# SHARKSKYFC.net
KiCad netlist of a schematic drawn in EAGLE
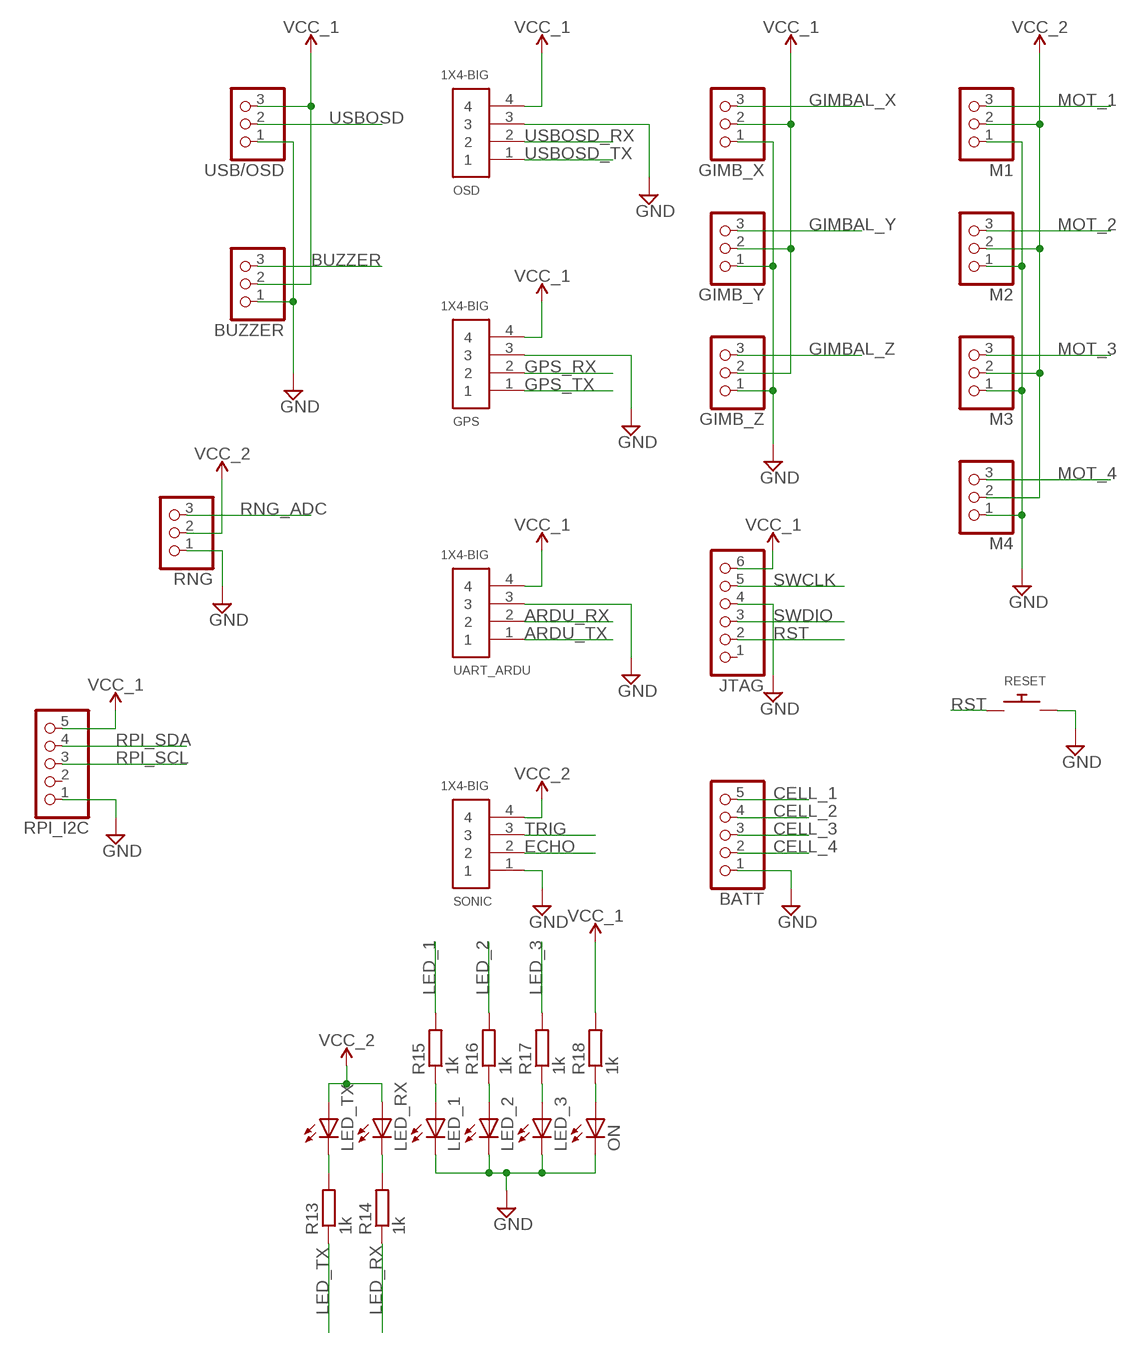
[diagram p0: schematic, sheet 1, part 1 of 2]
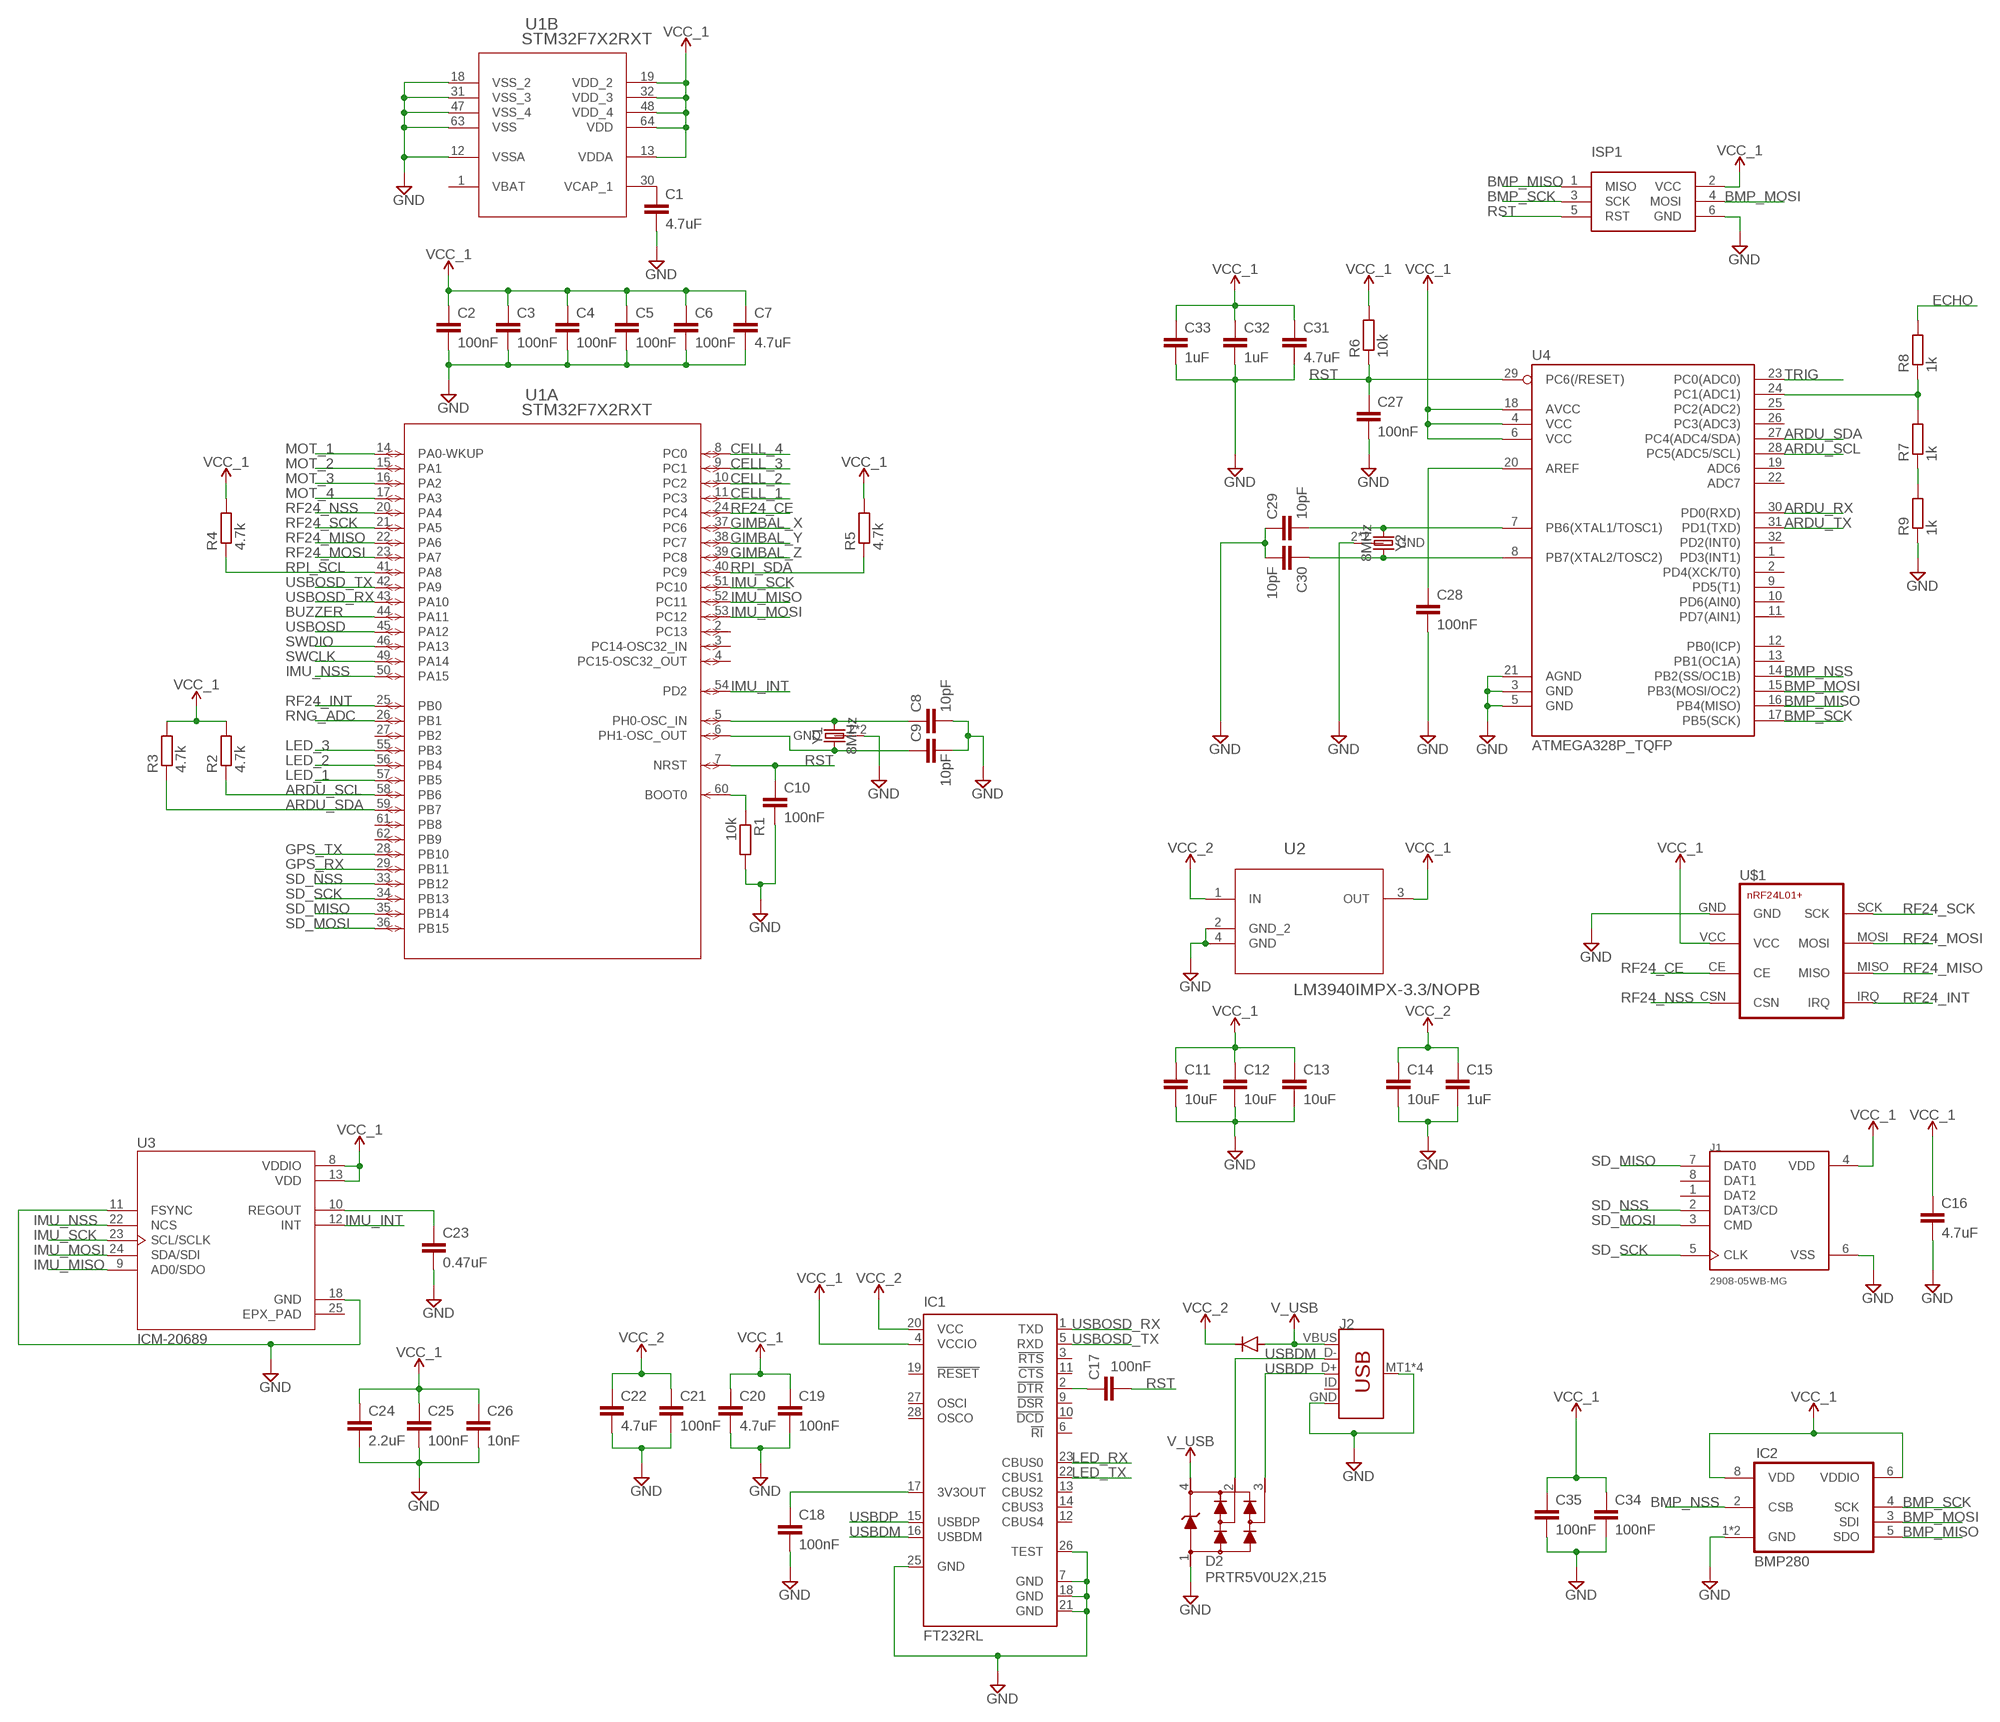
[diagram p1: schematic, sheet 1, part 2 of 2]

(export (version "E")
  (design (tool "Eeschema 10.0.6"))
  (components
    (comp (ref "BATT")
      (value "PINHD-1X5")
      (footprint "eagle-import:1X05")
      (libsource (lib "eagle-import") (part "PINHD-1X5"))
    )
    (comp (ref "BUZZER")
      (value "PINHD-1X3")
      (footprint "eagle-import:1X03")
      (libsource (lib "eagle-import") (part "PINHD-1X3"))
    )
    (comp (ref "C1")
      (value "4.7uF")
      (footprint "eagle-import:C0805")
      (libsource (lib "eagle-import") (part "C-EUC0805"))
    )
    (comp (ref "C2")
      (value "100nF")
      (footprint "eagle-import:C0805")
      (libsource (lib "eagle-import") (part "C-EUC0805"))
    )
    (comp (ref "C3")
      (value "100nF")
      (footprint "eagle-import:C0805")
      (libsource (lib "eagle-import") (part "C-EUC0805"))
    )
    (comp (ref "C4")
      (value "100nF")
      (footprint "eagle-import:C0805")
      (libsource (lib "eagle-import") (part "C-EUC0805"))
    )
    (comp (ref "C5")
      (value "100nF")
      (footprint "eagle-import:C0805")
      (libsource (lib "eagle-import") (part "C-EUC0805"))
    )
    (comp (ref "C6")
      (value "100nF")
      (footprint "eagle-import:C0805")
      (libsource (lib "eagle-import") (part "C-EUC0805"))
    )
    (comp (ref "C7")
      (value "4.7uF")
      (footprint "eagle-import:C0805")
      (libsource (lib "eagle-import") (part "C-EUC0805"))
    )
    (comp (ref "C8")
      (value "10pF")
      (footprint "eagle-import:C0805")
      (libsource (lib "eagle-import") (part "C-EUC0805"))
    )
    (comp (ref "C9")
      (value "10pF")
      (footprint "eagle-import:C0805")
      (libsource (lib "eagle-import") (part "C-EUC0805"))
    )
    (comp (ref "C10")
      (value "100nF")
      (footprint "eagle-import:C0805")
      (libsource (lib "eagle-import") (part "C-EUC0805"))
    )
    (comp (ref "C11")
      (value "10uF")
      (footprint "eagle-import:C0805")
      (libsource (lib "eagle-import") (part "C-EUC0805"))
    )
    (comp (ref "C12")
      (value "10uF")
      (footprint "eagle-import:C0805")
      (libsource (lib "eagle-import") (part "C-EUC0805"))
    )
    (comp (ref "C13")
      (value "10uF")
      (footprint "eagle-import:C0805")
      (libsource (lib "eagle-import") (part "C-EUC0805"))
    )
    (comp (ref "C14")
      (value "10uF")
      (footprint "eagle-import:C0805")
      (libsource (lib "eagle-import") (part "C-EUC0805"))
    )
    (comp (ref "C15")
      (value "1uF")
      (footprint "eagle-import:C0805")
      (libsource (lib "eagle-import") (part "C-EUC0805"))
    )
    (comp (ref "C16")
      (value "4.7uF")
      (footprint "eagle-import:C0805")
      (libsource (lib "eagle-import") (part "C-EUC0805"))
    )
    (comp (ref "C17")
      (value "100nF")
      (footprint "eagle-import:C0805")
      (libsource (lib "eagle-import") (part "C-EUC0805"))
    )
    (comp (ref "C18")
      (value "100nF")
      (footprint "eagle-import:C0805")
      (libsource (lib "eagle-import") (part "C-EUC0805"))
    )
    (comp (ref "C19")
      (value "100nF")
      (footprint "eagle-import:C0805")
      (libsource (lib "eagle-import") (part "C-EUC0805"))
    )
    (comp (ref "C20")
      (value "4.7uF")
      (footprint "eagle-import:C0805")
      (libsource (lib "eagle-import") (part "C-EUC0805"))
    )
    (comp (ref "C21")
      (value "100nF")
      (footprint "eagle-import:C0805")
      (libsource (lib "eagle-import") (part "C-EUC0805"))
    )
    (comp (ref "C22")
      (value "4.7uF")
      (footprint "eagle-import:C0805")
      (libsource (lib "eagle-import") (part "C-EUC0805"))
    )
    (comp (ref "C23")
      (value "0.47uF")
      (footprint "eagle-import:C0805")
      (libsource (lib "eagle-import") (part "C-EUC0805"))
    )
    (comp (ref "C24")
      (value "2.2uF")
      (footprint "eagle-import:C0805")
      (libsource (lib "eagle-import") (part "C-EUC0805"))
    )
    (comp (ref "C25")
      (value "100nF")
      (footprint "eagle-import:C0805")
      (libsource (lib "eagle-import") (part "C-EUC0805"))
    )
    (comp (ref "C26")
      (value "10nF")
      (footprint "eagle-import:C0805")
      (libsource (lib "eagle-import") (part "C-EUC0805"))
    )
    (comp (ref "C27")
      (value "100nF")
      (footprint "eagle-import:C0805")
      (libsource (lib "eagle-import") (part "C-EUC0805"))
    )
    (comp (ref "C28")
      (value "100nF")
      (footprint "eagle-import:C0805")
      (libsource (lib "eagle-import") (part "C-EUC0805"))
    )
    (comp (ref "C29")
      (value "10pF")
      (footprint "eagle-import:C0805")
      (libsource (lib "eagle-import") (part "C-EUC0805"))
    )
    (comp (ref "C30")
      (value "10pF")
      (footprint "eagle-import:C0805")
      (libsource (lib "eagle-import") (part "C-EUC0805"))
    )
    (comp (ref "C31")
      (value "4.7uF")
      (footprint "eagle-import:C0805")
      (libsource (lib "eagle-import") (part "C-EUC0805"))
    )
    (comp (ref "C32")
      (value "1uF")
      (footprint "eagle-import:C0805")
      (libsource (lib "eagle-import") (part "C-EUC0805"))
    )
    (comp (ref "C33")
      (value "1uF")
      (footprint "eagle-import:C0805")
      (libsource (lib "eagle-import") (part "C-EUC0805"))
    )
    (comp (ref "C34")
      (value "100nF")
      (footprint "eagle-import:C0805")
      (libsource (lib "eagle-import") (part "C-EUC0805"))
    )
    (comp (ref "C35")
      (value "100nF")
      (footprint "eagle-import:C0805")
      (libsource (lib "eagle-import") (part "C-EUC0805"))
    )
    (comp (ref "D1")
      (value "DIODE-DO214BA")
      (footprint "eagle-import:DO214BA")
      (libsource (lib "eagle-import") (part "DIODE-DO214BA"))
    )
    (comp (ref "D2")
      (value "PRTR5V0U2X,215")
      (footprint "eagle-import:SOT143B")
      (fields (field (name "MF") "Nexperia USA"))
      (libsource (lib "eagle-import") (part "PRTR5V0U2X,215"))
    )
    (comp (ref "GIMB_X")
      (value "PINHD-1X3")
      (footprint "eagle-import:1X03")
      (libsource (lib "eagle-import") (part "PINHD-1X3"))
    )
    (comp (ref "GIMB_Y")
      (value "PINHD-1X3")
      (footprint "eagle-import:1X03")
      (libsource (lib "eagle-import") (part "PINHD-1X3"))
    )
    (comp (ref "GIMB_Z")
      (value "PINHD-1X3")
      (footprint "eagle-import:1X03")
      (libsource (lib "eagle-import") (part "PINHD-1X3"))
    )
    (comp (ref "GPS")
      (value "1X4-BIG")
      (footprint "eagle-import:1X04-BIG")
      (libsource (lib "eagle-import") (part "1X4-BIG"))
    )
    (comp (ref "IC1")
      (value "FT232RL")
      (footprint "eagle-import:SSOP28")
      (libsource (lib "eagle-import") (part "FT232RL"))
    )
    (comp (ref "IC2")
      (value "BMP280")
      (footprint "eagle-import:BMP280")
      (libsource (lib "eagle-import") (part "BMP280"))
    )
    (comp (ref "ISP1")
      (value "AVRISP-6")
      (footprint "eagle-import:AVRISP")
      (libsource (lib "eagle-import") (part "AVRISP-6"))
    )
    (comp (ref "J1")
      (value "2908-05WB-MG")
      (footprint "eagle-import:3M_2908-05WB-MG")
      (fields (field (name "MF") "3M"))
      (libsource (lib "eagle-import") (part "2908-05WB-MG"))
    )
    (comp (ref "J2")
      (value "USB_MICRO-B_SMT")
      (footprint "eagle-import:USB-MICROB")
      (libsource (lib "eagle-import") (part "USB_MICRO-B_SMT"))
    )
    (comp (ref "JTAG")
      (value "PINHD-1X6")
      (footprint "eagle-import:1X06")
      (libsource (lib "eagle-import") (part "PINHD-1X6"))
    )
    (comp (ref "LED_1")
      (value "LEDSMT1206")
      (footprint "eagle-import:1206")
      (libsource (lib "eagle-import") (part "LEDSMT1206"))
    )
    (comp (ref "LED_2")
      (value "LEDSMT1206")
      (footprint "eagle-import:1206")
      (libsource (lib "eagle-import") (part "LEDSMT1206"))
    )
    (comp (ref "LED_3")
      (value "LEDSMT1206")
      (footprint "eagle-import:1206")
      (libsource (lib "eagle-import") (part "LEDSMT1206"))
    )
    (comp (ref "LED_RX")
      (value "LEDSMT1206")
      (footprint "eagle-import:1206")
      (libsource (lib "eagle-import") (part "LEDSMT1206"))
    )
    (comp (ref "LED_TX")
      (value "LEDSMT1206")
      (footprint "eagle-import:1206")
      (libsource (lib "eagle-import") (part "LEDSMT1206"))
    )
    (comp (ref "M1")
      (value "PINHD-1X3")
      (footprint "eagle-import:1X03")
      (libsource (lib "eagle-import") (part "PINHD-1X3"))
    )
    (comp (ref "M2")
      (value "PINHD-1X3")
      (footprint "eagle-import:1X03")
      (libsource (lib "eagle-import") (part "PINHD-1X3"))
    )
    (comp (ref "M3")
      (value "PINHD-1X3")
      (footprint "eagle-import:1X03")
      (libsource (lib "eagle-import") (part "PINHD-1X3"))
    )
    (comp (ref "M4")
      (value "PINHD-1X3")
      (footprint "eagle-import:1X03")
      (libsource (lib "eagle-import") (part "PINHD-1X3"))
    )
    (comp (ref "ON")
      (value "LEDSMT1206")
      (footprint "eagle-import:1206")
      (libsource (lib "eagle-import") (part "LEDSMT1206"))
    )
    (comp (ref "OSD")
      (value "1X4-BIG")
      (footprint "eagle-import:1X04-BIG")
      (libsource (lib "eagle-import") (part "1X4-BIG"))
    )
    (comp (ref "R1")
      (value "10k")
      (footprint "eagle-import:R0603")
      (libsource (lib "eagle-import") (part "R-EU_R0603"))
    )
    (comp (ref "R2")
      (value "4.7k")
      (footprint "eagle-import:R0603")
      (libsource (lib "eagle-import") (part "R-EU_R0603"))
    )
    (comp (ref "R3")
      (value "4.7k")
      (footprint "eagle-import:R0603")
      (libsource (lib "eagle-import") (part "R-EU_R0603"))
    )
    (comp (ref "R4")
      (value "4.7k")
      (footprint "eagle-import:R0603")
      (libsource (lib "eagle-import") (part "R-EU_R0603"))
    )
    (comp (ref "R5")
      (value "4.7k")
      (footprint "eagle-import:R0603")
      (libsource (lib "eagle-import") (part "R-EU_R0603"))
    )
    (comp (ref "R6")
      (value "10k")
      (footprint "eagle-import:R0603")
      (libsource (lib "eagle-import") (part "R-EU_R0603"))
    )
    (comp (ref "R7")
      (value "1k")
      (footprint "eagle-import:R0603")
      (libsource (lib "eagle-import") (part "R-EU_R0603"))
    )
    (comp (ref "R8")
      (value "1k")
      (footprint "eagle-import:R0603")
      (libsource (lib "eagle-import") (part "R-EU_R0603"))
    )
    (comp (ref "R9")
      (value "1k")
      (footprint "eagle-import:R0603")
      (libsource (lib "eagle-import") (part "R-EU_R0603"))
    )
    (comp (ref "R13")
      (value "1k")
      (footprint "eagle-import:R0603")
      (libsource (lib "eagle-import") (part "R-EU_R0603"))
    )
    (comp (ref "R14")
      (value "1k")
      (footprint "eagle-import:R0603")
      (libsource (lib "eagle-import") (part "R-EU_R0603"))
    )
    (comp (ref "R15")
      (value "1k")
      (footprint "eagle-import:R0603")
      (libsource (lib "eagle-import") (part "R-EU_R0603"))
    )
    (comp (ref "R16")
      (value "1k")
      (footprint "eagle-import:R0603")
      (libsource (lib "eagle-import") (part "R-EU_R0603"))
    )
    (comp (ref "R17")
      (value "1k")
      (footprint "eagle-import:R0603")
      (libsource (lib "eagle-import") (part "R-EU_R0603"))
    )
    (comp (ref "R18")
      (value "1k")
      (footprint "eagle-import:R0603")
      (libsource (lib "eagle-import") (part "R-EU_R0603"))
    )
    (comp (ref "RESET")
      (value "SWITCH_PUSHBUTTONC&K_KSS")
      (footprint "eagle-import:BTN_CK_KSS")
      (libsource (lib "eagle-import") (part "SWITCH_PUSHBUTTONC&K_KSS"))
    )
    (comp (ref "RNG")
      (value "PINHD-1X3")
      (footprint "eagle-import:1X03")
      (libsource (lib "eagle-import") (part "PINHD-1X3"))
    )
    (comp (ref "RPI_I2C")
      (value "PINHD-1X5")
      (footprint "eagle-import:1X05")
      (libsource (lib "eagle-import") (part "PINHD-1X5"))
    )
    (comp (ref "SONIC")
      (value "1X4-BIG")
      (footprint "eagle-import:1X04-BIG")
      (libsource (lib "eagle-import") (part "1X4-BIG"))
    )
    (comp (ref "U$1")
      (value "NRF24L01+")
      (footprint "eagle-import:NRF24L01+")
      (libsource (lib "eagle-import") (part "NRF24L01+"))
    )
    (comp (ref "U1")
      (value "STM32F7X2RXT")
      (footprint "eagle-import:LQFP64-10X10MM")
      (libsource (lib "eagle-import") (part "STM32F7X2RXT"))
    )
    (comp (ref "U2")
      (value "LM3940IMPX-3.3/NOPB")
      (footprint "eagle-import:SOT230P696X180-4N")
      (fields (field (name "MF") "Texas Instruments"))
      (libsource (lib "eagle-import") (part "LM3940IMPX-3.3/NOPB"))
    )
    (comp (ref "U3")
      (value "ICM-20689")
      (footprint "eagle-import:QFN50P400X400X95-25N")
      (fields (field (name "MF") "TDK InvenSense"))
      (libsource (lib "eagle-import") (part "ICM-20689"))
    )
    (comp (ref "U4")
      (value "ATMEGA328P_TQFP")
      (footprint "eagle-import:TQFP32-08")
      (libsource (lib "eagle-import") (part "ATMEGA328P_TQFP"))
    )
    (comp (ref "UART_ARDU")
      (value "1X4-BIG")
      (footprint "eagle-import:1X04-BIG")
      (libsource (lib "eagle-import") (part "1X4-BIG"))
    )
    (comp (ref "USB/OSD")
      (value "PINHD-1X3")
      (footprint "eagle-import:1X03")
      (libsource (lib "eagle-import") (part "PINHD-1X3"))
    )
    (comp (ref "Y1")
      (value "8MHz")
      (footprint "eagle-import:CRYSTAL-SMD-5X3.2-4PAD")
      (libsource (lib "eagle-import") (part "CRYSTAL-8MHZSMD-5X3.2"))
    )
    (comp (ref "Y2")
      (value "8MHz")
      (footprint "eagle-import:CRYSTAL-SMD-5X3.2-4PAD")
      (libsource (lib "eagle-import") (part "CRYSTAL-8MHZSMD-5X3.2"))
    )
  )
  (nets
    (net (code "1") (name "/ARDU_RX") (class "Default")
      (node (ref "U4") (pin "30") (pinfunction "PD0(RXD)_30") (pintype "bidirectional"))
      (node (ref "UART_ARDU") (pin "2") (pinfunction "2_2") (pintype "bidirectional"))
    )
    (net (code "2") (name "/ARDU_SCL") (class "Default")
      (node (ref "R2") (pin "1") (pinfunction "1_1") (pintype "passive"))
      (node (ref "U1") (pin "58") (pinfunction "PB6_58") (pintype "bidirectional"))
      (node (ref "U4") (pin "28") (pinfunction "PC5(ADC5/SCL)_28") (pintype "bidirectional"))
    )
    (net (code "3") (name "/ARDU_SDA") (class "Default")
      (node (ref "R3") (pin "1") (pinfunction "1_1") (pintype "passive"))
      (node (ref "U1") (pin "59") (pinfunction "PB7_59") (pintype "bidirectional"))
      (node (ref "U4") (pin "27") (pinfunction "PC4(ADC4/SDA)_27") (pintype "bidirectional"))
    )
    (net (code "4") (name "/ARDU_TX") (class "Default")
      (node (ref "U4") (pin "31") (pinfunction "PD1(TXD)_31") (pintype "bidirectional"))
      (node (ref "UART_ARDU") (pin "1") (pinfunction "1_1") (pintype "bidirectional"))
    )
    (net (code "5") (name "/BMP_MISO") (class "Default")
      (node (ref "IC2") (pin "5") (pinfunction "SDO_5") (pintype "input"))
      (node (ref "ISP1") (pin "1") (pinfunction "MISO_1") (pintype "input"))
      (node (ref "U4") (pin "16") (pinfunction "PB4(MISO)_16") (pintype "bidirectional"))
    )
    (net (code "6") (name "/BMP_MOSI") (class "Default")
      (node (ref "IC2") (pin "3") (pinfunction "SDI_3") (pintype "bidirectional"))
      (node (ref "ISP1") (pin "4") (pinfunction "MOSI_4") (pintype "output"))
      (node (ref "U4") (pin "15") (pinfunction "PB3(MOSI/OC2)_15") (pintype "bidirectional"))
    )
    (net (code "7") (name "/BMP_NSS") (class "Default")
      (node (ref "IC2") (pin "2") (pinfunction "CSB_2") (pintype "input"))
      (node (ref "U4") (pin "14") (pinfunction "PB2(SS/OC1B)_14") (pintype "bidirectional"))
    )
    (net (code "8") (name "/BMP_SCK") (class "Default")
      (node (ref "IC2") (pin "4") (pinfunction "SCK_4") (pintype "bidirectional"))
      (node (ref "ISP1") (pin "3") (pinfunction "SCK_3") (pintype "output"))
      (node (ref "U4") (pin "17") (pinfunction "PB5(SCK)_17") (pintype "bidirectional"))
    )
    (net (code "9") (name "/BUZZER") (class "Default")
      (node (ref "BUZZER") (pin "3") (pinfunction "3_3") (pintype "passive"))
      (node (ref "U1") (pin "44") (pinfunction "PA11_44") (pintype "bidirectional"))
    )
    (net (code "10") (name "/CELL_1") (class "Default")
      (node (ref "BATT") (pin "5") (pinfunction "5_5") (pintype "passive"))
      (node (ref "U1") (pin "11") (pinfunction "PC3_11") (pintype "bidirectional"))
    )
    (net (code "11") (name "/CELL_2") (class "Default")
      (node (ref "BATT") (pin "4") (pinfunction "4_4") (pintype "passive"))
      (node (ref "U1") (pin "10") (pinfunction "PC2_10") (pintype "bidirectional"))
    )
    (net (code "12") (name "/CELL_3") (class "Default")
      (node (ref "BATT") (pin "3") (pinfunction "3_3") (pintype "passive"))
      (node (ref "U1") (pin "9") (pinfunction "PC1_9") (pintype "bidirectional"))
    )
    (net (code "13") (name "/CELL_4") (class "Default")
      (node (ref "BATT") (pin "2") (pinfunction "2_2") (pintype "passive"))
      (node (ref "U1") (pin "8") (pinfunction "PC0_8") (pintype "bidirectional"))
    )
    (net (code "14") (name "/ECHO") (class "Default")
      (node (ref "R8") (pin "2") (pinfunction "2_2") (pintype "passive"))
      (node (ref "SONIC") (pin "2") (pinfunction "2_2") (pintype "bidirectional"))
    )
    (net (code "15") (name "/EPX_PAD") (class "Default")
      (node (ref "U3") (pin "25") (pinfunction "EPX_PAD_25") (pintype "power_in"))
    )
    (net (code "16") (name "/GIMBAL_X") (class "Default")
      (node (ref "GIMB_X") (pin "3") (pinfunction "3_3") (pintype "passive"))
      (node (ref "U1") (pin "37") (pinfunction "PC6_37") (pintype "bidirectional"))
    )
    (net (code "17") (name "/GIMBAL_Y") (class "Default")
      (node (ref "GIMB_Y") (pin "3") (pinfunction "3_3") (pintype "passive"))
      (node (ref "U1") (pin "38") (pinfunction "PC7_38") (pintype "bidirectional"))
    )
    (net (code "18") (name "/GIMBAL_Z") (class "Default")
      (node (ref "GIMB_Z") (pin "3") (pinfunction "3_3") (pintype "passive"))
      (node (ref "U1") (pin "39") (pinfunction "PC8_39") (pintype "bidirectional"))
    )
    (net (code "19") (name "/GPS_RX") (class "Default")
      (node (ref "GPS") (pin "2") (pinfunction "2_2") (pintype "bidirectional"))
      (node (ref "U1") (pin "29") (pinfunction "PB11_29") (pintype "bidirectional"))
    )
    (net (code "20") (name "/GPS_TX") (class "Default")
      (node (ref "GPS") (pin "1") (pinfunction "1_1") (pintype "bidirectional"))
      (node (ref "U1") (pin "28") (pinfunction "PB10_28") (pintype "bidirectional"))
    )
    (net (code "21") (name "/IMU_INT") (class "Default")
      (node (ref "U1") (pin "54") (pinfunction "PD2_54") (pintype "bidirectional"))
      (node (ref "U3") (pin "12") (pinfunction "INT_12") (pintype "output"))
    )
    (net (code "22") (name "/IMU_MISO") (class "Default")
      (node (ref "U1") (pin "52") (pinfunction "PC11_52") (pintype "bidirectional"))
      (node (ref "U3") (pin "9") (pinfunction "AD0/SDO_9") (pintype "bidirectional"))
    )
    (net (code "23") (name "/IMU_MOSI") (class "Default")
      (node (ref "U1") (pin "53") (pinfunction "PC12_53") (pintype "bidirectional"))
      (node (ref "U3") (pin "24") (pinfunction "SDA/SDI_24") (pintype "bidirectional"))
    )
    (net (code "24") (name "/IMU_NSS") (class "Default")
      (node (ref "U1") (pin "50") (pinfunction "PA15_50") (pintype "bidirectional"))
      (node (ref "U3") (pin "22") (pinfunction "NCS_22") (pintype "input"))
    )
    (net (code "25") (name "/IMU_SCK") (class "Default")
      (node (ref "U1") (pin "51") (pinfunction "PC10_51") (pintype "bidirectional"))
      (node (ref "U3") (pin "23") (pinfunction "SCL/SCLK_23") (pintype "input"))
    )
    (net (code "26") (name "/LED_1") (class "Default")
      (node (ref "R15") (pin "2") (pinfunction "2_2") (pintype "passive"))
      (node (ref "U1") (pin "57") (pinfunction "PB5_57") (pintype "bidirectional"))
    )
    (net (code "27") (name "/LED_2") (class "Default")
      (node (ref "R16") (pin "2") (pinfunction "2_2") (pintype "passive"))
      (node (ref "U1") (pin "56") (pinfunction "PB4_56") (pintype "bidirectional"))
    )
    (net (code "28") (name "/LED_3") (class "Default")
      (node (ref "R17") (pin "2") (pinfunction "2_2") (pintype "passive"))
      (node (ref "U1") (pin "55") (pinfunction "PB3_55") (pintype "bidirectional"))
    )
    (net (code "29") (name "/LED_RX") (class "Default")
      (node (ref "IC1") (pin "23") (pinfunction "CBUS0_23") (pintype "bidirectional"))
      (node (ref "R14") (pin "1") (pinfunction "1_1") (pintype "passive"))
    )
    (net (code "30") (name "/LED_TX") (class "Default")
      (node (ref "IC1") (pin "22") (pinfunction "CBUS1_22") (pintype "bidirectional"))
      (node (ref "R13") (pin "1") (pinfunction "1_1") (pintype "passive"))
    )
    (net (code "31") (name "/MOT_1") (class "Default")
      (node (ref "M1") (pin "3") (pinfunction "3_3") (pintype "passive"))
      (node (ref "U1") (pin "14") (pinfunction "PA0-WKUP_14") (pintype "bidirectional"))
    )
    (net (code "32") (name "/MOT_2") (class "Default")
      (node (ref "M2") (pin "3") (pinfunction "3_3") (pintype "passive"))
      (node (ref "U1") (pin "15") (pinfunction "PA1_15") (pintype "bidirectional"))
    )
    (net (code "33") (name "/MOT_3") (class "Default")
      (node (ref "M3") (pin "3") (pinfunction "3_3") (pintype "passive"))
      (node (ref "U1") (pin "16") (pinfunction "PA2_16") (pintype "bidirectional"))
    )
    (net (code "34") (name "/MOT_4") (class "Default")
      (node (ref "M4") (pin "3") (pinfunction "3_3") (pintype "passive"))
      (node (ref "U1") (pin "17") (pinfunction "PA3_17") (pintype "bidirectional"))
    )
    (net (code "35") (name "/RF24_CE") (class "Default")
      (node (ref "U$1") (pin "CE") (pinfunction "CE_CE") (pintype "bidirectional"))
      (node (ref "U1") (pin "24") (pinfunction "PC4_24") (pintype "bidirectional"))
    )
    (net (code "36") (name "/RF24_INT") (class "Default")
      (node (ref "U$1") (pin "IRQ") (pinfunction "IRQ_IRQ") (pintype "bidirectional"))
      (node (ref "U1") (pin "25") (pinfunction "PB0_25") (pintype "bidirectional"))
    )
    (net (code "37") (name "/RF24_MISO") (class "Default")
      (node (ref "U$1") (pin "MISO") (pinfunction "MISO_MISO") (pintype "bidirectional"))
      (node (ref "U1") (pin "22") (pinfunction "PA6_22") (pintype "bidirectional"))
    )
    (net (code "38") (name "/RF24_MOSI") (class "Default")
      (node (ref "U$1") (pin "MOSI") (pinfunction "MOSI_MOSI") (pintype "bidirectional"))
      (node (ref "U1") (pin "23") (pinfunction "PA7_23") (pintype "bidirectional"))
    )
    (net (code "39") (name "/RF24_NSS") (class "Default")
      (node (ref "U$1") (pin "CSN") (pinfunction "CSN_CSN") (pintype "bidirectional"))
      (node (ref "U1") (pin "20") (pinfunction "PA4_20") (pintype "bidirectional"))
    )
    (net (code "40") (name "/RF24_SCK") (class "Default")
      (node (ref "U$1") (pin "SCK") (pinfunction "SCK_SCK") (pintype "bidirectional"))
      (node (ref "U1") (pin "21") (pinfunction "PA5_21") (pintype "bidirectional"))
    )
    (net (code "41") (name "/RNG_ADC") (class "Default")
      (node (ref "RNG") (pin "3") (pinfunction "3_3") (pintype "passive"))
      (node (ref "U1") (pin "26") (pinfunction "PB1_26") (pintype "bidirectional"))
    )
    (net (code "42") (name "/RPI_SCL") (class "Default")
      (node (ref "R4") (pin "1") (pinfunction "1_1") (pintype "passive"))
      (node (ref "RPI_I2C") (pin "3") (pinfunction "3_3") (pintype "passive"))
      (node (ref "U1") (pin "41") (pinfunction "PA8_41") (pintype "bidirectional"))
    )
    (net (code "43") (name "/RPI_SDA") (class "Default")
      (node (ref "R5") (pin "1") (pinfunction "1_1") (pintype "passive"))
      (node (ref "RPI_I2C") (pin "4") (pinfunction "4_4") (pintype "passive"))
      (node (ref "U1") (pin "40") (pinfunction "PC9_40") (pintype "bidirectional"))
    )
    (net (code "44") (name "/RST") (class "Default")
      (node (ref "C10") (pin "1") (pinfunction "1_1") (pintype "passive"))
      (node (ref "C17") (pin "2") (pinfunction "2_2") (pintype "passive"))
      (node (ref "C27") (pin "1") (pinfunction "1_1") (pintype "passive"))
      (node (ref "ISP1") (pin "5") (pinfunction "RST_5") (pintype "output"))
      (node (ref "JTAG") (pin "2") (pinfunction "2_2") (pintype "passive"))
      (node (ref "R6") (pin "1") (pinfunction "1_1") (pintype "passive"))
      (node (ref "RESET") (pin "P$1") (pinfunction "P$1_P$1") (pintype "passive"))
      (node (ref "U1") (pin "7") (pinfunction "NRST_7") (pintype "bidirectional"))
      (node (ref "U4") (pin "29") (pinfunction "PC6(/RESET)_29") (pintype "bidirectional"))
    )
    (net (code "45") (name "/SD_MISO") (class "Default")
      (node (ref "J1") (pin "7") (pinfunction "DAT0_7") (pintype "bidirectional"))
      (node (ref "U1") (pin "35") (pinfunction "PB14_35") (pintype "bidirectional"))
    )
    (net (code "46") (name "/SD_MOSI") (class "Default")
      (node (ref "J1") (pin "3") (pinfunction "CMD_3") (pintype "bidirectional"))
      (node (ref "U1") (pin "36") (pinfunction "PB15_36") (pintype "bidirectional"))
    )
    (net (code "47") (name "/SD_NSS") (class "Default")
      (node (ref "J1") (pin "2") (pinfunction "DAT3/CD_2") (pintype "bidirectional"))
      (node (ref "U1") (pin "33") (pinfunction "PB12_33") (pintype "bidirectional"))
    )
    (net (code "48") (name "/SD_SCK") (class "Default")
      (node (ref "J1") (pin "5") (pinfunction "CLK_5") (pintype "bidirectional"))
      (node (ref "U1") (pin "34") (pinfunction "PB13_34") (pintype "bidirectional"))
    )
    (net (code "49") (name "/SWCLK") (class "Default")
      (node (ref "JTAG") (pin "5") (pinfunction "5_5") (pintype "passive"))
      (node (ref "U1") (pin "49") (pinfunction "PA14_49") (pintype "bidirectional"))
    )
    (net (code "50") (name "/SWDIO") (class "Default")
      (node (ref "JTAG") (pin "3") (pinfunction "3_3") (pintype "passive"))
      (node (ref "U1") (pin "46") (pinfunction "PA13_46") (pintype "bidirectional"))
    )
    (net (code "51") (name "/TRIG") (class "Default")
      (node (ref "SONIC") (pin "3") (pinfunction "3_3") (pintype "bidirectional"))
      (node (ref "U4") (pin "23") (pinfunction "PC0(ADC0)_23") (pintype "bidirectional"))
    )
    (net (code "52") (name "/USBDM") (class "Default")
      (node (ref "D2") (pin "2") (pinfunction "P$2_2") (pintype "passive"))
      (node (ref "IC1") (pin "16") (pinfunction "USBDM_16") (pintype "bidirectional"))
      (node (ref "J2") (pin "D-") (pinfunction "D-_D-") (pintype "bidirectional"))
    )
    (net (code "53") (name "/USBDP") (class "Default")
      (node (ref "D2") (pin "3") (pinfunction "P$3_3") (pintype "passive"))
      (node (ref "IC1") (pin "15") (pinfunction "USBDP_15") (pintype "bidirectional"))
      (node (ref "J2") (pin "D+") (pinfunction "D+_D+") (pintype "bidirectional"))
    )
    (net (code "54") (name "/USBOSD") (class "Default")
      (node (ref "U1") (pin "45") (pinfunction "PA12_45") (pintype "bidirectional"))
      (node (ref "USB/OSD") (pin "2") (pinfunction "2_2") (pintype "passive"))
    )
    (net (code "55") (name "/USBOSD_RX") (class "Default")
      (node (ref "IC1") (pin "1") (pinfunction "TXD_1") (pintype "output"))
      (node (ref "OSD") (pin "2") (pinfunction "2_2") (pintype "bidirectional"))
      (node (ref "U1") (pin "43") (pinfunction "PA10_43") (pintype "bidirectional"))
    )
    (net (code "56") (name "/USBOSD_TX") (class "Default")
      (node (ref "IC1") (pin "5") (pinfunction "RXD_5") (pintype "input"))
      (node (ref "OSD") (pin "1") (pinfunction "1_1") (pintype "bidirectional"))
      (node (ref "U1") (pin "42") (pinfunction "PA9_42") (pintype "bidirectional"))
    )
    (net (code "57") (name "/VBAT") (class "Default")
      (node (ref "U1") (pin "1") (pinfunction "VBAT_1") (pintype "power_in"))
    )
    (net (code "58") (name "GND") (class "Default")
      (node (ref "BATT") (pin "1") (pinfunction "1_1") (pintype "passive"))
      (node (ref "BUZZER") (pin "1") (pinfunction "1_1") (pintype "passive"))
      (node (ref "C1") (pin "2") (pinfunction "2_2") (pintype "passive"))
      (node (ref "C10") (pin "2") (pinfunction "2_2") (pintype "passive"))
      (node (ref "C11") (pin "2") (pinfunction "2_2") (pintype "passive"))
      (node (ref "C12") (pin "2") (pinfunction "2_2") (pintype "passive"))
      (node (ref "C13") (pin "2") (pinfunction "2_2") (pintype "passive"))
      (node (ref "C14") (pin "2") (pinfunction "2_2") (pintype "passive"))
      (node (ref "C15") (pin "2") (pinfunction "2_2") (pintype "passive"))
      (node (ref "C16") (pin "2") (pinfunction "2_2") (pintype "passive"))
      (node (ref "C18") (pin "2") (pinfunction "2_2") (pintype "passive"))
      (node (ref "C19") (pin "2") (pinfunction "2_2") (pintype "passive"))
      (node (ref "C2") (pin "2") (pinfunction "2_2") (pintype "passive"))
      (node (ref "C20") (pin "2") (pinfunction "2_2") (pintype "passive"))
      (node (ref "C21") (pin "2") (pinfunction "2_2") (pintype "passive"))
      (node (ref "C22") (pin "2") (pinfunction "2_2") (pintype "passive"))
      (node (ref "C23") (pin "2") (pinfunction "2_2") (pintype "passive"))
      (node (ref "C24") (pin "2") (pinfunction "2_2") (pintype "passive"))
      (node (ref "C25") (pin "2") (pinfunction "2_2") (pintype "passive"))
      (node (ref "C26") (pin "2") (pinfunction "2_2") (pintype "passive"))
      (node (ref "C27") (pin "2") (pinfunction "2_2") (pintype "passive"))
      (node (ref "C28") (pin "2") (pinfunction "2_2") (pintype "passive"))
      (node (ref "C29") (pin "1") (pinfunction "1_1") (pintype "passive"))
      (node (ref "C3") (pin "2") (pinfunction "2_2") (pintype "passive"))
      (node (ref "C30") (pin "2") (pinfunction "2_2") (pintype "passive"))
      (node (ref "C31") (pin "2") (pinfunction "2_2") (pintype "passive"))
      (node (ref "C32") (pin "2") (pinfunction "2_2") (pintype "passive"))
      (node (ref "C33") (pin "2") (pinfunction "2_2") (pintype "passive"))
      (node (ref "C34") (pin "2") (pinfunction "2_2") (pintype "passive"))
      (node (ref "C35") (pin "2") (pinfunction "2_2") (pintype "passive"))
      (node (ref "C4") (pin "2") (pinfunction "2_2") (pintype "passive"))
      (node (ref "C5") (pin "2") (pinfunction "2_2") (pintype "passive"))
      (node (ref "C6") (pin "2") (pinfunction "2_2") (pintype "passive"))
      (node (ref "C7") (pin "2") (pinfunction "2_2") (pintype "passive"))
      (node (ref "C8") (pin "2") (pinfunction "2_2") (pintype "passive"))
      (node (ref "C9") (pin "2") (pinfunction "2_2") (pintype "passive"))
      (node (ref "D2") (pin "1") (pinfunction "P$1_1") (pintype "passive"))
      (node (ref "GIMB_X") (pin "1") (pinfunction "1_1") (pintype "passive"))
      (node (ref "GIMB_Y") (pin "1") (pinfunction "1_1") (pintype "passive"))
      (node (ref "GIMB_Z") (pin "1") (pinfunction "1_1") (pintype "passive"))
      (node (ref "GPS") (pin "3") (pinfunction "3_3") (pintype "bidirectional"))
      (node (ref "IC1") (pin "18") (pinfunction "GND_18") (pintype "power_in"))
      (node (ref "IC1") (pin "21") (pinfunction "GND_21") (pintype "power_in"))
      (node (ref "IC1") (pin "25") (pinfunction "GND_25") (pintype "power_in"))
      (node (ref "IC1") (pin "26") (pinfunction "TEST_26") (pintype "input"))
      (node (ref "IC1") (pin "7") (pinfunction "GND_7") (pintype "power_in"))
      (node (ref "IC2") (pin "1") (pinfunction "GND_1") (pintype "power_in"))
      (node (ref "IC2") (pin "7") (pinfunction "GND_7") (pintype "power_in"))
      (node (ref "ISP1") (pin "6") (pinfunction "GND_6") (pintype "power_in"))
      (node (ref "J1") (pin "6") (pinfunction "VSS_6") (pintype "power_in"))
      (node (ref "J2") (pin "GND") (pinfunction "GND_GND") (pintype "power_in"))
      (node (ref "J2") (pin "MT1") (pinfunction "SHIELD_MT1") (pintype "bidirectional"))
      (node (ref "J2") (pin "MT2") (pinfunction "SHIELD_MT2") (pintype "bidirectional"))
      (node (ref "J2") (pin "P$1") (pinfunction "SHIELD_P$1") (pintype "bidirectional"))
      (node (ref "J2") (pin "P$2") (pinfunction "SHIELD_P$2") (pintype "bidirectional"))
      (node (ref "JTAG") (pin "4") (pinfunction "4_4") (pintype "passive"))
      (node (ref "LED_1") (pin "C") (pinfunction "C_C") (pintype "passive"))
      (node (ref "LED_2") (pin "C") (pinfunction "C_C") (pintype "passive"))
      (node (ref "LED_3") (pin "C") (pinfunction "C_C") (pintype "passive"))
      (node (ref "M1") (pin "1") (pinfunction "1_1") (pintype "passive"))
      (node (ref "M2") (pin "1") (pinfunction "1_1") (pintype "passive"))
      (node (ref "M3") (pin "1") (pinfunction "1_1") (pintype "passive"))
      (node (ref "M4") (pin "1") (pinfunction "1_1") (pintype "passive"))
      (node (ref "ON") (pin "C") (pinfunction "C_C") (pintype "passive"))
      (node (ref "OSD") (pin "3") (pinfunction "3_3") (pintype "bidirectional"))
      (node (ref "R1") (pin "2") (pinfunction "2_2") (pintype "passive"))
      (node (ref "R9") (pin "1") (pinfunction "1_1") (pintype "passive"))
      (node (ref "RESET") (pin "P$2") (pinfunction "P$2_P$2") (pintype "passive"))
      (node (ref "RNG") (pin "1") (pinfunction "1_1") (pintype "passive"))
      (node (ref "RPI_I2C") (pin "1") (pinfunction "1_1") (pintype "passive"))
      (node (ref "SONIC") (pin "1") (pinfunction "1_1") (pintype "bidirectional"))
      (node (ref "U$1") (pin "GND") (pinfunction "GND_GND") (pintype "power_in"))
      (node (ref "U1") (pin "12") (pinfunction "VSSA_12") (pintype "power_in"))
      (node (ref "U1") (pin "18") (pinfunction "VSS_2_18") (pintype "power_in"))
      (node (ref "U1") (pin "31") (pinfunction "VSS_3_31") (pintype "power_in"))
      (node (ref "U1") (pin "47") (pinfunction "VSS_4_47") (pintype "power_in"))
      (node (ref "U1") (pin "63") (pinfunction "VSS_63") (pintype "power_in"))
      (node (ref "U2") (pin "2") (pinfunction "GND_2_2") (pintype "passive"))
      (node (ref "U2") (pin "4") (pinfunction "GND_4") (pintype "passive"))
      (node (ref "U3") (pin "11") (pinfunction "FSYNC_11") (pintype "input"))
      (node (ref "U3") (pin "18") (pinfunction "GND_18") (pintype "power_in"))
      (node (ref "U4") (pin "21") (pinfunction "AGND_21") (pintype "bidirectional"))
      (node (ref "U4") (pin "3") (pinfunction "GND_3") (pintype "bidirectional"))
      (node (ref "U4") (pin "5") (pinfunction "GND_5") (pintype "bidirectional"))
      (node (ref "UART_ARDU") (pin "3") (pinfunction "3_3") (pintype "bidirectional"))
      (node (ref "USB/OSD") (pin "1") (pinfunction "1_1") (pintype "passive"))
      (node (ref "Y1") (pin "2") (pinfunction "GND_2") (pintype "bidirectional"))
      (node (ref "Y1") (pin "4") (pinfunction "GND_4") (pintype "bidirectional"))
      (node (ref "Y2") (pin "2") (pinfunction "GND_2") (pintype "bidirectional"))
      (node (ref "Y2") (pin "4") (pinfunction "GND_4") (pintype "bidirectional"))
    )
    (net (code "59") (name "Net-(IC1-3V3OUT)") (class "Default")
      (node (ref "C18") (pin "1") (pinfunction "1_1") (pintype "passive"))
      (node (ref "IC1") (pin "17") (pinfunction "3V3OUT_17") (pintype "output"))
    )
    (net (code "60") (name "Net-(IC1-~{DTR})") (class "Default")
      (node (ref "C17") (pin "1") (pinfunction "1_1") (pintype "passive"))
      (node (ref "IC1") (pin "2") (pinfunction "~{DTR}_2") (pintype "output"))
    )
    (net (code "61") (name "Net-(LED_1-PadA)") (class "Default")
      (node (ref "LED_1") (pin "A") (pinfunction "A_A") (pintype "passive"))
      (node (ref "R15") (pin "1") (pinfunction "1_1") (pintype "passive"))
    )
    (net (code "62") (name "Net-(LED_2-PadA)") (class "Default")
      (node (ref "LED_2") (pin "A") (pinfunction "A_A") (pintype "passive"))
      (node (ref "R16") (pin "1") (pinfunction "1_1") (pintype "passive"))
    )
    (net (code "63") (name "Net-(LED_3-PadA)") (class "Default")
      (node (ref "LED_3") (pin "A") (pinfunction "A_A") (pintype "passive"))
      (node (ref "R17") (pin "1") (pinfunction "1_1") (pintype "passive"))
    )
    (net (code "64") (name "Net-(LED_RX-PadC)") (class "Default")
      (node (ref "LED_RX") (pin "C") (pinfunction "C_C") (pintype "passive"))
      (node (ref "R14") (pin "2") (pinfunction "2_2") (pintype "passive"))
    )
    (net (code "65") (name "Net-(LED_TX-PadC)") (class "Default")
      (node (ref "LED_TX") (pin "C") (pinfunction "C_C") (pintype "passive"))
      (node (ref "R13") (pin "2") (pinfunction "2_2") (pintype "passive"))
    )
    (net (code "66") (name "Net-(ON-PadA)") (class "Default")
      (node (ref "ON") (pin "A") (pinfunction "A_A") (pintype "passive"))
      (node (ref "R18") (pin "1") (pinfunction "1_1") (pintype "passive"))
    )
    (net (code "67") (name "Net-(R7-Pad1)") (class "Default")
      (node (ref "R7") (pin "1") (pinfunction "1_1") (pintype "passive"))
      (node (ref "R9") (pin "2") (pinfunction "2_2") (pintype "passive"))
    )
    (net (code "68") (name "Net-(U1A-BOOT0)") (class "Default")
      (node (ref "R1") (pin "1") (pinfunction "1_1") (pintype "passive"))
      (node (ref "U1") (pin "60") (pinfunction "BOOT0_60") (pintype "input"))
    )
    (net (code "69") (name "Net-(U1A-PH0-OSC_IN)") (class "Default")
      (node (ref "C8") (pin "1") (pinfunction "1_1") (pintype "passive"))
      (node (ref "U1") (pin "5") (pinfunction "PH0-OSC_IN_5") (pintype "bidirectional"))
      (node (ref "Y1") (pin "3") (pinfunction "2_3") (pintype "passive"))
    )
    (net (code "70") (name "Net-(U1A-PH1-OSC_OUT)") (class "Default")
      (node (ref "C9") (pin "1") (pinfunction "1_1") (pintype "passive"))
      (node (ref "U1") (pin "6") (pinfunction "PH1-OSC_OUT_6") (pintype "bidirectional"))
      (node (ref "Y1") (pin "1") (pinfunction "1_1") (pintype "passive"))
    )
    (net (code "71") (name "Net-(U1B-VCAP_1)") (class "Default")
      (node (ref "C1") (pin "1") (pinfunction "1_1") (pintype "passive"))
      (node (ref "U1") (pin "30") (pinfunction "VCAP_1_30") (pintype "power_in"))
    )
    (net (code "72") (name "Net-(U3-REGOUT)") (class "Default")
      (node (ref "C23") (pin "1") (pinfunction "1_1") (pintype "passive"))
      (node (ref "U3") (pin "10") (pinfunction "REGOUT_10") (pintype "output"))
    )
    (net (code "73") (name "Net-(U4-AREF)") (class "Default")
      (node (ref "C28") (pin "1") (pinfunction "1_1") (pintype "passive"))
      (node (ref "U4") (pin "20") (pinfunction "AREF_20") (pintype "bidirectional"))
    )
    (net (code "74") (name "Net-(U4-PB6(XTAL1{slash}TOSC1))") (class "Default")
      (node (ref "C29") (pin "2") (pinfunction "2_2") (pintype "passive"))
      (node (ref "U4") (pin "7") (pinfunction "PB6(XTAL1/TOSC1)_7") (pintype "bidirectional"))
      (node (ref "Y2") (pin "1") (pinfunction "1_1") (pintype "passive"))
    )
    (net (code "75") (name "Net-(U4-PB7(XTAL2{slash}TOSC2))") (class "Default")
      (node (ref "C30") (pin "1") (pinfunction "1_1") (pintype "passive"))
      (node (ref "U4") (pin "8") (pinfunction "PB7(XTAL2/TOSC2)_8") (pintype "bidirectional"))
      (node (ref "Y2") (pin "3") (pinfunction "2_3") (pintype "passive"))
    )
    (net (code "76") (name "Net-(U4-PC1(ADC1))") (class "Default")
      (node (ref "R7") (pin "2") (pinfunction "2_2") (pintype "passive"))
      (node (ref "R8") (pin "1") (pinfunction "1_1") (pintype "passive"))
      (node (ref "U4") (pin "24") (pinfunction "PC1(ADC1)_24") (pintype "bidirectional"))
    )
    (net (code "77") (name "VCC_1") (class "Default")
      (node (ref "BUZZER") (pin "2") (pinfunction "2_2") (pintype "passive"))
      (node (ref "C11") (pin "1") (pinfunction "1_1") (pintype "passive"))
      (node (ref "C12") (pin "1") (pinfunction "1_1") (pintype "passive"))
      (node (ref "C13") (pin "1") (pinfunction "1_1") (pintype "passive"))
      (node (ref "C16") (pin "1") (pinfunction "1_1") (pintype "passive"))
      (node (ref "C19") (pin "1") (pinfunction "1_1") (pintype "passive"))
      (node (ref "C2") (pin "1") (pinfunction "1_1") (pintype "passive"))
      (node (ref "C20") (pin "1") (pinfunction "1_1") (pintype "passive"))
      (node (ref "C24") (pin "1") (pinfunction "1_1") (pintype "passive"))
      (node (ref "C25") (pin "1") (pinfunction "1_1") (pintype "passive"))
      (node (ref "C26") (pin "1") (pinfunction "1_1") (pintype "passive"))
      (node (ref "C3") (pin "1") (pinfunction "1_1") (pintype "passive"))
      (node (ref "C31") (pin "1") (pinfunction "1_1") (pintype "passive"))
      (node (ref "C32") (pin "1") (pinfunction "1_1") (pintype "passive"))
      (node (ref "C33") (pin "1") (pinfunction "1_1") (pintype "passive"))
      (node (ref "C34") (pin "1") (pinfunction "1_1") (pintype "passive"))
      (node (ref "C35") (pin "1") (pinfunction "1_1") (pintype "passive"))
      (node (ref "C4") (pin "1") (pinfunction "1_1") (pintype "passive"))
      (node (ref "C5") (pin "1") (pinfunction "1_1") (pintype "passive"))
      (node (ref "C6") (pin "1") (pinfunction "1_1") (pintype "passive"))
      (node (ref "C7") (pin "1") (pinfunction "1_1") (pintype "passive"))
      (node (ref "GIMB_X") (pin "2") (pinfunction "2_2") (pintype "passive"))
      (node (ref "GIMB_Y") (pin "2") (pinfunction "2_2") (pintype "passive"))
      (node (ref "GIMB_Z") (pin "2") (pinfunction "2_2") (pintype "passive"))
      (node (ref "GPS") (pin "4") (pinfunction "4_4") (pintype "bidirectional"))
      (node (ref "IC1") (pin "4") (pinfunction "VCCIO_4") (pintype "power_in"))
      (node (ref "IC2") (pin "6") (pinfunction "VDDIO_6") (pintype "power_in"))
      (node (ref "IC2") (pin "8") (pinfunction "VDD_8") (pintype "power_in"))
      (node (ref "ISP1") (pin "2") (pinfunction "VCC_2") (pintype "power_in"))
      (node (ref "J1") (pin "4") (pinfunction "VDD_4") (pintype "power_in"))
      (node (ref "JTAG") (pin "6") (pinfunction "6_6") (pintype "passive"))
      (node (ref "OSD") (pin "4") (pinfunction "4_4") (pintype "bidirectional"))
      (node (ref "R18") (pin "2") (pinfunction "2_2") (pintype "passive"))
      (node (ref "R2") (pin "2") (pinfunction "2_2") (pintype "passive"))
      (node (ref "R3") (pin "2") (pinfunction "2_2") (pintype "passive"))
      (node (ref "R4") (pin "2") (pinfunction "2_2") (pintype "passive"))
      (node (ref "R5") (pin "2") (pinfunction "2_2") (pintype "passive"))
      (node (ref "R6") (pin "2") (pinfunction "2_2") (pintype "passive"))
      (node (ref "RPI_I2C") (pin "5") (pinfunction "5_5") (pintype "passive"))
      (node (ref "U$1") (pin "VCC") (pinfunction "VCC_VCC") (pintype "power_in"))
      (node (ref "U1") (pin "13") (pinfunction "VDDA_13") (pintype "power_in"))
      (node (ref "U1") (pin "19") (pinfunction "VDD_2_19") (pintype "power_in"))
      (node (ref "U1") (pin "32") (pinfunction "VDD_3_32") (pintype "power_in"))
      (node (ref "U1") (pin "48") (pinfunction "VDD_4_48") (pintype "power_in"))
      (node (ref "U1") (pin "64") (pinfunction "VDD_64") (pintype "power_in"))
      (node (ref "U2") (pin "3") (pinfunction "OUT_3") (pintype "output"))
      (node (ref "U3") (pin "13") (pinfunction "VDD_13") (pintype "power_in"))
      (node (ref "U3") (pin "8") (pinfunction "VDDIO_8") (pintype "power_in"))
      (node (ref "U4") (pin "18") (pinfunction "AVCC_18") (pintype "bidirectional"))
      (node (ref "U4") (pin "4") (pinfunction "VCC_4") (pintype "bidirectional"))
      (node (ref "U4") (pin "6") (pinfunction "VCC_6") (pintype "bidirectional"))
      (node (ref "UART_ARDU") (pin "4") (pinfunction "4_4") (pintype "bidirectional"))
      (node (ref "USB/OSD") (pin "3") (pinfunction "3_3") (pintype "passive"))
    )
    (net (code "78") (name "VCC_2") (class "Default")
      (node (ref "C14") (pin "1") (pinfunction "1_1") (pintype "passive"))
      (node (ref "C15") (pin "1") (pinfunction "1_1") (pintype "passive"))
      (node (ref "C21") (pin "1") (pinfunction "1_1") (pintype "passive"))
      (node (ref "C22") (pin "1") (pinfunction "1_1") (pintype "passive"))
      (node (ref "D1") (pin "C") (pinfunction "C_C") (pintype "passive"))
      (node (ref "IC1") (pin "20") (pinfunction "VCC_20") (pintype "power_in"))
      (node (ref "LED_RX") (pin "A") (pinfunction "A_A") (pintype "passive"))
      (node (ref "LED_TX") (pin "A") (pinfunction "A_A") (pintype "passive"))
      (node (ref "M1") (pin "2") (pinfunction "2_2") (pintype "passive"))
      (node (ref "M2") (pin "2") (pinfunction "2_2") (pintype "passive"))
      (node (ref "M3") (pin "2") (pinfunction "2_2") (pintype "passive"))
      (node (ref "M4") (pin "2") (pinfunction "2_2") (pintype "passive"))
      (node (ref "RNG") (pin "2") (pinfunction "2_2") (pintype "passive"))
      (node (ref "SONIC") (pin "4") (pinfunction "4_4") (pintype "bidirectional"))
      (node (ref "U2") (pin "1") (pinfunction "IN_1") (pintype "power_in"))
    )
    (net (code "79") (name "V_USB") (class "Default")
      (node (ref "D1") (pin "A") (pinfunction "A_A") (pintype "passive"))
      (node (ref "D2") (pin "4") (pinfunction "P$4_4") (pintype "passive"))
      (node (ref "J2") (pin "VBUS") (pinfunction "VBUS_VBUS") (pintype "power_in"))
    )
    (net (code "80") (name "unconnected-(IC1-CBUS2-Pad13)") (class "Default")
      (node (ref "IC1") (pin "13") (pinfunction "CBUS2_13") (pintype "bidirectional"))
    )
    (net (code "81") (name "unconnected-(IC1-CBUS3-Pad14)") (class "Default")
      (node (ref "IC1") (pin "14") (pinfunction "CBUS3_14") (pintype "bidirectional"))
    )
    (net (code "82") (name "unconnected-(IC1-CBUS4-Pad12)") (class "Default")
      (node (ref "IC1") (pin "12") (pinfunction "CBUS4_12") (pintype "bidirectional"))
    )
    (net (code "83") (name "unconnected-(IC1-OSCI-Pad27)") (class "Default")
      (node (ref "IC1") (pin "27") (pinfunction "OSCI_27") (pintype "input"))
    )
    (net (code "84") (name "unconnected-(IC1-OSCO-Pad28)") (class "Default")
      (node (ref "IC1") (pin "28") (pinfunction "OSCO_28") (pintype "output"))
    )
    (net (code "85") (name "unconnected-(IC1-~{CTS}-Pad11)") (class "Default")
      (node (ref "IC1") (pin "11") (pinfunction "~{CTS}_11") (pintype "input"))
    )
    (net (code "86") (name "unconnected-(IC1-~{DCD}-Pad10)") (class "Default")
      (node (ref "IC1") (pin "10") (pinfunction "~{DCD}_10") (pintype "input"))
    )
    (net (code "87") (name "unconnected-(IC1-~{DSR}-Pad9)") (class "Default")
      (node (ref "IC1") (pin "9") (pinfunction "~{DSR}_9") (pintype "input"))
    )
    (net (code "88") (name "unconnected-(IC1-~{RESET}-Pad19)") (class "Default")
      (node (ref "IC1") (pin "19") (pinfunction "~{RESET}_19") (pintype "input"))
    )
    (net (code "89") (name "unconnected-(IC1-~{RI}-Pad6)") (class "Default")
      (node (ref "IC1") (pin "6") (pinfunction "~{RI}_6") (pintype "input"))
    )
    (net (code "90") (name "unconnected-(IC1-~{RTS}-Pad3)") (class "Default")
      (node (ref "IC1") (pin "3") (pinfunction "~{RTS}_3") (pintype "output"))
    )
    (net (code "91") (name "unconnected-(J1-DAT1-Pad8)") (class "Default")
      (node (ref "J1") (pin "8") (pinfunction "DAT1_8") (pintype "bidirectional"))
    )
    (net (code "92") (name "unconnected-(J1-DAT2-Pad1)") (class "Default")
      (node (ref "J1") (pin "1") (pinfunction "DAT2_1") (pintype "bidirectional"))
    )
    (net (code "93") (name "unconnected-(J2-PadID)") (class "Default")
      (node (ref "J2") (pin "ID") (pinfunction "ID_ID") (pintype "bidirectional"))
    )
    (net (code "94") (name "unconnected-(JTAG-Pad1)") (class "Default")
      (node (ref "JTAG") (pin "1") (pinfunction "1_1") (pintype "passive"))
    )
    (net (code "95") (name "unconnected-(RPI_I2C-Pad2)") (class "Default")
      (node (ref "RPI_I2C") (pin "2") (pinfunction "2_2") (pintype "passive"))
    )
    (net (code "96") (name "unconnected-(U1A-PB2-Pad27)") (class "Default")
      (node (ref "U1") (pin "27") (pinfunction "PB2_27") (pintype "bidirectional"))
    )
    (net (code "97") (name "unconnected-(U1A-PB8-Pad61)") (class "Default")
      (node (ref "U1") (pin "61") (pinfunction "PB8_61") (pintype "bidirectional"))
    )
    (net (code "98") (name "unconnected-(U1A-PB9-Pad62)") (class "Default")
      (node (ref "U1") (pin "62") (pinfunction "PB9_62") (pintype "bidirectional"))
    )
    (net (code "99") (name "unconnected-(U1A-PC13-Pad2)") (class "Default")
      (node (ref "U1") (pin "2") (pinfunction "PC13_2") (pintype "bidirectional"))
    )
    (net (code "100") (name "unconnected-(U1A-PC14-OSC32_IN-Pad3)") (class "Default")
      (node (ref "U1") (pin "3") (pinfunction "PC14-OSC32_IN_3") (pintype "bidirectional"))
    )
    (net (code "101") (name "unconnected-(U1A-PC15-OSC32_OUT-Pad4)") (class "Default")
      (node (ref "U1") (pin "4") (pinfunction "PC15-OSC32_OUT_4") (pintype "bidirectional"))
    )
    (net (code "102") (name "unconnected-(U4-ADC6-Pad19)") (class "Default")
      (node (ref "U4") (pin "19") (pinfunction "ADC6_19") (pintype "bidirectional"))
    )
    (net (code "103") (name "unconnected-(U4-ADC7-Pad22)") (class "Default")
      (node (ref "U4") (pin "22") (pinfunction "ADC7_22") (pintype "bidirectional"))
    )
    (net (code "104") (name "unconnected-(U4-PB0(ICP)-Pad12)") (class "Default")
      (node (ref "U4") (pin "12") (pinfunction "PB0(ICP)_12") (pintype "bidirectional"))
    )
    (net (code "105") (name "unconnected-(U4-PB1(OC1A)-Pad13)") (class "Default")
      (node (ref "U4") (pin "13") (pinfunction "PB1(OC1A)_13") (pintype "bidirectional"))
    )
    (net (code "106") (name "unconnected-(U4-PC2(ADC2)-Pad25)") (class "Default")
      (node (ref "U4") (pin "25") (pinfunction "PC2(ADC2)_25") (pintype "bidirectional"))
    )
    (net (code "107") (name "unconnected-(U4-PC3(ADC3)-Pad26)") (class "Default")
      (node (ref "U4") (pin "26") (pinfunction "PC3(ADC3)_26") (pintype "bidirectional"))
    )
    (net (code "108") (name "unconnected-(U4-PD2(INT0)-Pad32)") (class "Default")
      (node (ref "U4") (pin "32") (pinfunction "PD2(INT0)_32") (pintype "bidirectional"))
    )
    (net (code "109") (name "unconnected-(U4-PD3(INT1)-Pad1)") (class "Default")
      (node (ref "U4") (pin "1") (pinfunction "PD3(INT1)_1") (pintype "bidirectional"))
    )
    (net (code "110") (name "unconnected-(U4-PD4(XCK{slash}T0)-Pad2)") (class "Default")
      (node (ref "U4") (pin "2") (pinfunction "PD4(XCK/T0)_2") (pintype "bidirectional"))
    )
    (net (code "111") (name "unconnected-(U4-PD5(T1)-Pad9)") (class "Default")
      (node (ref "U4") (pin "9") (pinfunction "PD5(T1)_9") (pintype "bidirectional"))
    )
    (net (code "112") (name "unconnected-(U4-PD6(AIN0)-Pad10)") (class "Default")
      (node (ref "U4") (pin "10") (pinfunction "PD6(AIN0)_10") (pintype "bidirectional"))
    )
    (net (code "113") (name "unconnected-(U4-PD7(AIN1)-Pad11)") (class "Default")
      (node (ref "U4") (pin "11") (pinfunction "PD7(AIN1)_11") (pintype "bidirectional"))
    )
  )
)
